# bms_board.net
KiCad netlist of a schematic drawn in EAGLE
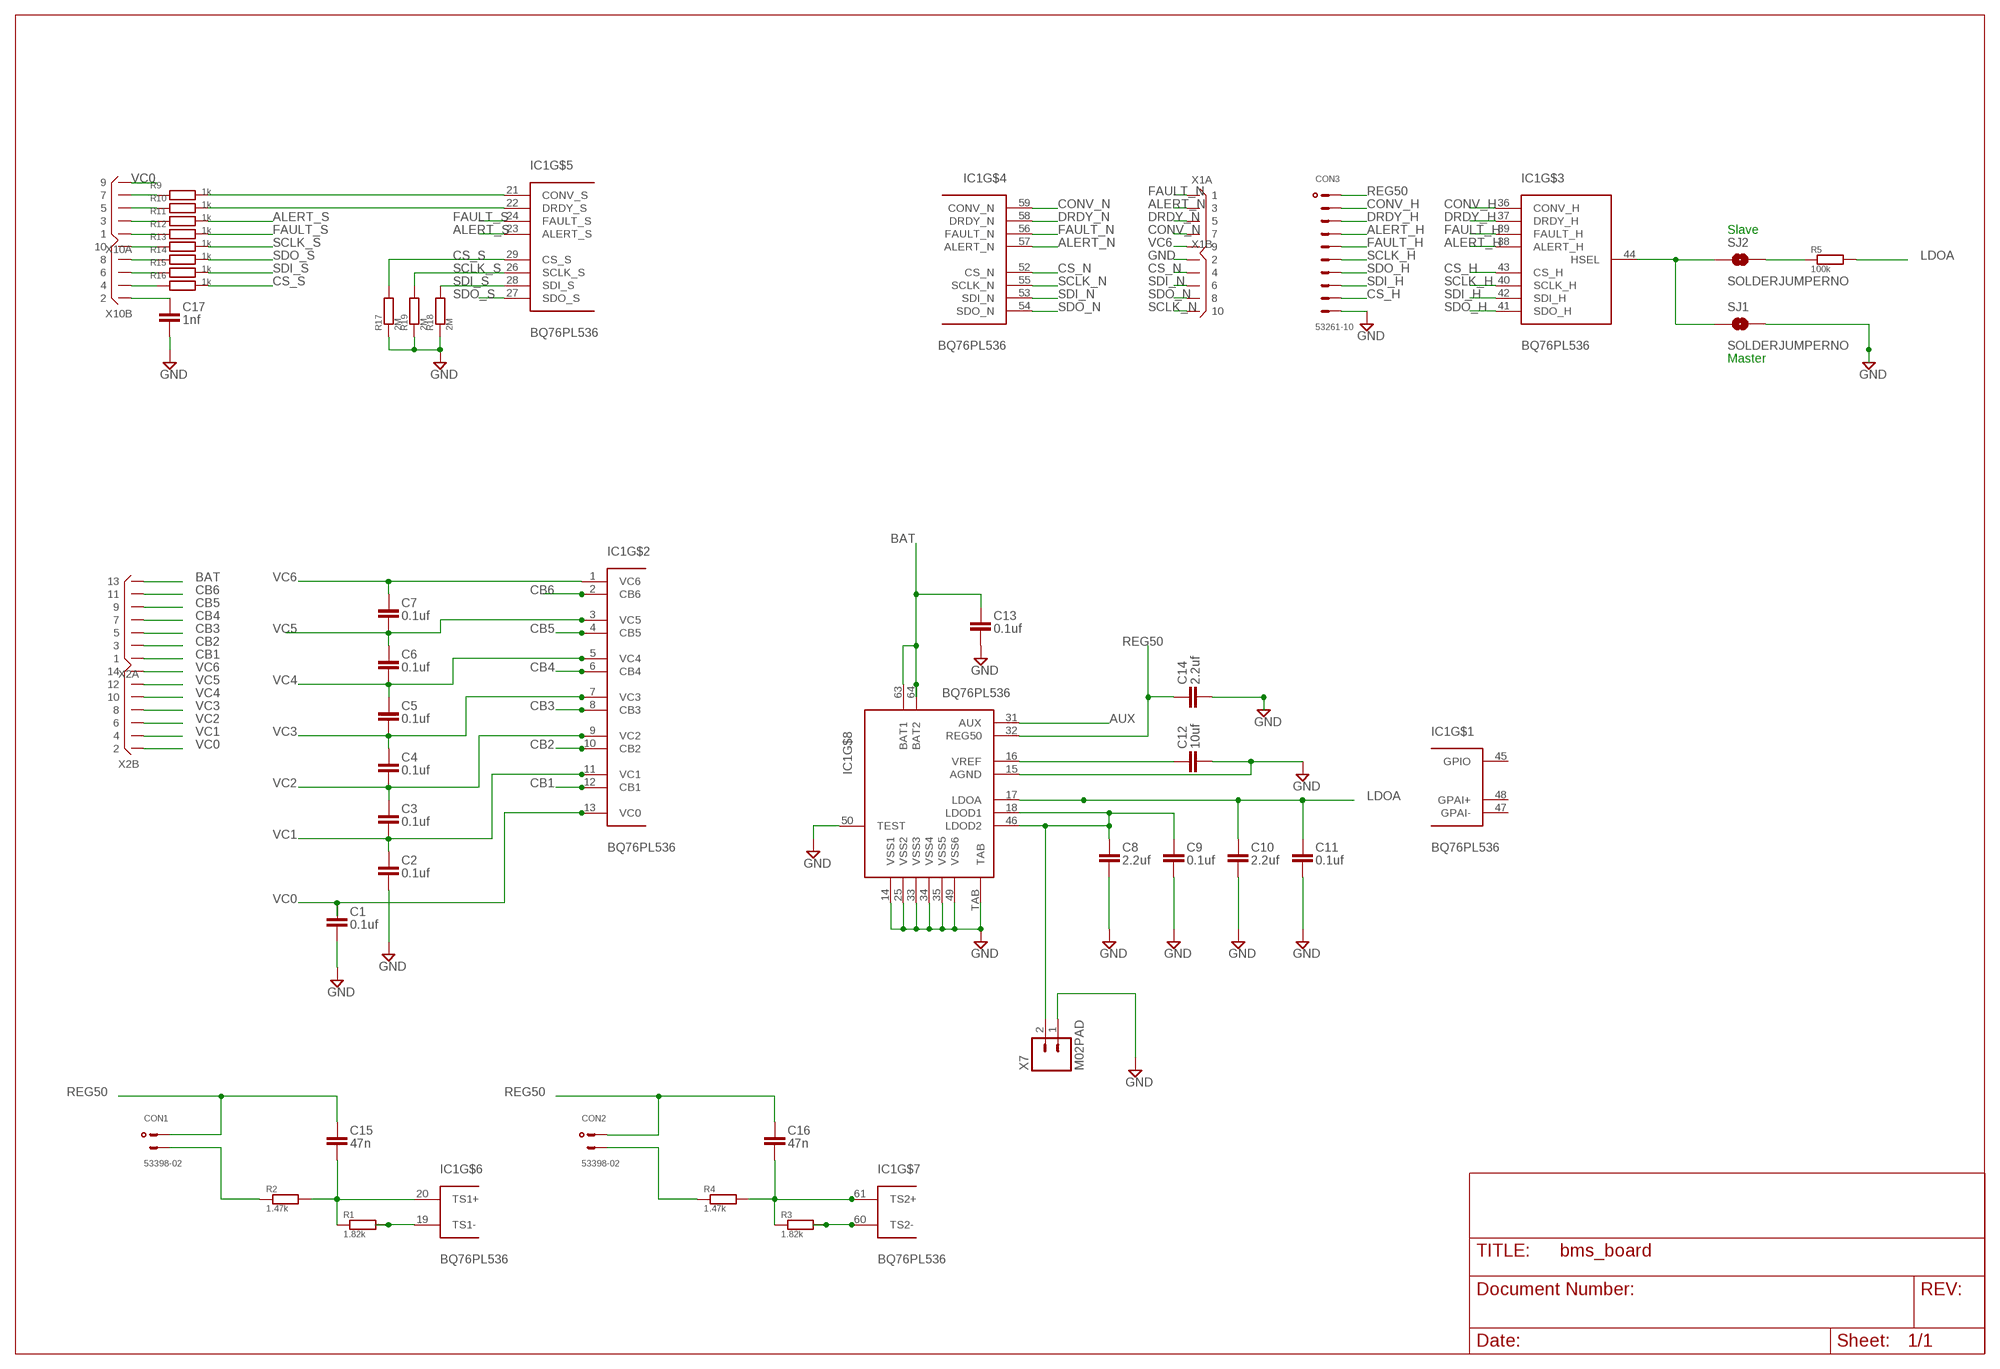
[diagram p0: schematic, sheet 1]

(export (version "E")
  (design (tool "Eeschema 10.0.6"))
  (components
    (comp (ref "C1")
      (value "0.1uf")
      (footprint "eagle-import:C0805")
      (libsource (lib "eagle-import") (part "CSTD"))
    )
    (comp (ref "C2")
      (value "0.1uf")
      (footprint "eagle-import:C0805")
      (libsource (lib "eagle-import") (part "CSTD"))
    )
    (comp (ref "C3")
      (value "0.1uf")
      (footprint "eagle-import:C0805")
      (libsource (lib "eagle-import") (part "CSTD"))
    )
    (comp (ref "C4")
      (value "0.1uf")
      (footprint "eagle-import:C0805")
      (libsource (lib "eagle-import") (part "CSTD"))
    )
    (comp (ref "C5")
      (value "0.1uf")
      (footprint "eagle-import:C0805")
      (libsource (lib "eagle-import") (part "CSTD"))
    )
    (comp (ref "C6")
      (value "0.1uf")
      (footprint "eagle-import:C0805")
      (libsource (lib "eagle-import") (part "CSTD"))
    )
    (comp (ref "C7")
      (value "0.1uf")
      (footprint "eagle-import:C0805")
      (libsource (lib "eagle-import") (part "CSTD"))
    )
    (comp (ref "C8")
      (value "2.2uf")
      (footprint "eagle-import:C0805")
      (libsource (lib "eagle-import") (part "CSTD"))
    )
    (comp (ref "C9")
      (value "0.1uf")
      (footprint "eagle-import:C0805")
      (libsource (lib "eagle-import") (part "CSTD"))
    )
    (comp (ref "C10")
      (value "2.2uf")
      (footprint "eagle-import:C0805")
      (libsource (lib "eagle-import") (part "CSTD"))
    )
    (comp (ref "C11")
      (value "0.1uf")
      (footprint "eagle-import:C0805")
      (libsource (lib "eagle-import") (part "CSTD"))
    )
    (comp (ref "C12")
      (value "10uf")
      (footprint "eagle-import:C0805")
      (libsource (lib "eagle-import") (part "CSTD"))
    )
    (comp (ref "C13")
      (value "0.1uf")
      (footprint "eagle-import:C0805")
      (libsource (lib "eagle-import") (part "CSTD"))
    )
    (comp (ref "C14")
      (value "2.2uf")
      (footprint "eagle-import:C0805")
      (libsource (lib "eagle-import") (part "CSTD"))
    )
    (comp (ref "C15")
      (value "47n")
      (footprint "eagle-import:C0805")
      (libsource (lib "eagle-import") (part "CSTD"))
    )
    (comp (ref "C16")
      (value "47n")
      (footprint "eagle-import:C0805")
      (libsource (lib "eagle-import") (part "CSTD"))
    )
    (comp (ref "C17")
      (value "1nf")
      (footprint "eagle-import:C0805")
      (libsource (lib "eagle-import") (part "CSTD"))
    )
    (comp (ref "CON1")
      (value "53398-02")
      (footprint "eagle-import:53398-02")
      (libsource (lib "eagle-import") (part "53?-02398"))
    )
    (comp (ref "CON2")
      (value "53398-02")
      (footprint "eagle-import:53398-02")
      (libsource (lib "eagle-import") (part "53?-02398"))
    )
    (comp (ref "CON3")
      (value "53261-10")
      (footprint "eagle-import:53261-10")
      (libsource (lib "eagle-import") (part "53?-10261"))
    )
    (comp (ref "IC1")
      (value "BQ76PL536")
      (footprint "eagle-import:LQFP-64")
      (libsource (lib "eagle-import") (part "BQ76PL536"))
    )
    (comp (ref "R1")
      (value "1.82k")
      (footprint "eagle-import:R0805")
      (libsource (lib "eagle-import") (part "R"))
    )
    (comp (ref "R2")
      (value "1.47k")
      (footprint "eagle-import:R0805")
      (libsource (lib "eagle-import") (part "R"))
    )
    (comp (ref "R3")
      (value "1.82k")
      (footprint "eagle-import:R0805")
      (libsource (lib "eagle-import") (part "R"))
    )
    (comp (ref "R4")
      (value "1.47k")
      (footprint "eagle-import:R0805")
      (libsource (lib "eagle-import") (part "R"))
    )
    (comp (ref "R5")
      (value "100k")
      (footprint "eagle-import:R0805")
      (libsource (lib "eagle-import") (part "R"))
    )
    (comp (ref "R9")
      (value "1k")
      (footprint "eagle-import:R0805")
      (libsource (lib "eagle-import") (part "R"))
    )
    (comp (ref "R10")
      (value "1k")
      (footprint "eagle-import:R0805")
      (libsource (lib "eagle-import") (part "R"))
    )
    (comp (ref "R11")
      (value "1k")
      (footprint "eagle-import:R0805")
      (libsource (lib "eagle-import") (part "R"))
    )
    (comp (ref "R12")
      (value "1k")
      (footprint "eagle-import:R0805")
      (libsource (lib "eagle-import") (part "R"))
    )
    (comp (ref "R13")
      (value "1k")
      (footprint "eagle-import:R0805")
      (libsource (lib "eagle-import") (part "R"))
    )
    (comp (ref "R14")
      (value "1k")
      (footprint "eagle-import:R0805")
      (libsource (lib "eagle-import") (part "R"))
    )
    (comp (ref "R15")
      (value "1k")
      (footprint "eagle-import:R0805")
      (libsource (lib "eagle-import") (part "R"))
    )
    (comp (ref "R16")
      (value "1k")
      (footprint "eagle-import:R0805")
      (libsource (lib "eagle-import") (part "R"))
    )
    (comp (ref "R17")
      (value "2M")
      (footprint "eagle-import:R0805")
      (libsource (lib "eagle-import") (part "R"))
    )
    (comp (ref "R18")
      (value "2M")
      (footprint "eagle-import:R0805")
      (libsource (lib "eagle-import") (part "R"))
    )
    (comp (ref "R19")
      (value "2M")
      (footprint "eagle-import:R0805")
      (libsource (lib "eagle-import") (part "R"))
    )
    (comp (ref "SJ1")
      (value "SOLDERJUMPERNO")
      (footprint "eagle-import:SJ_2S-NO")
      (libsource (lib "eagle-import") (part "SOLDERJUMPERNO"))
    )
    (comp (ref "SJ2")
      (value "SOLDERJUMPERNO")
      (footprint "eagle-import:SJ_2S-NO")
      (libsource (lib "eagle-import") (part "SOLDERJUMPERNO"))
    )
    (comp (ref "X1")
      (value "X05X2ICR")
      (footprint "eagle-import:X10ICR")
      (libsource (lib "eagle-import") (part "X05X2ICR"))
    )
    (comp (ref "X2")
      (value "X07X2IR")
      (footprint "eagle-import:X14R-IDC")
      (libsource (lib "eagle-import") (part "X07X2IR"))
    )
    (comp (ref "X7")
      (value "M02PAD")
      (footprint "eagle-import:1X02")
      (libsource (lib "eagle-import") (part "M02PAD"))
    )
    (comp (ref "X10")
      (value "X05X2ICR")
      (footprint "eagle-import:X10ICR")
      (libsource (lib "eagle-import") (part "X05X2ICR"))
    )
  )
  (nets
    (net (code "1") (name "/ALERT_H") (class "Default")
      (node (ref "CON3") (pin "4") (pinfunction "4_4") (pintype "passive"))
      (node (ref "IC1") (pin "38") (pinfunction "ALERT_H_38") (pintype "bidirectional"))
    )
    (net (code "2") (name "/ALERT_N") (class "Default")
      (node (ref "IC1") (pin "57") (pinfunction "ALERT_N_57") (pintype "bidirectional"))
      (node (ref "X1") (pin "3") (pinfunction "3_3") (pintype "bidirectional"))
    )
    (net (code "3") (name "/ALERT_S") (class "Default")
      (node (ref "IC1") (pin "23") (pinfunction "ALERT_S_23") (pintype "bidirectional"))
      (node (ref "R11") (pin "2") (pinfunction "2_2") (pintype "passive"))
    )
    (net (code "4") (name "/AUX") (class "Default")
      (node (ref "IC1") (pin "31") (pinfunction "AUX_31") (pintype "bidirectional"))
    )
    (net (code "5") (name "/BAT") (class "Default")
      (node (ref "C13") (pin "2") (pinfunction "2_2") (pintype "passive"))
      (node (ref "IC1") (pin "63") (pinfunction "BAT1_63") (pintype "bidirectional"))
      (node (ref "IC1") (pin "64") (pinfunction "BAT2_64") (pintype "bidirectional"))
      (node (ref "X2") (pin "13") (pinfunction "13_13") (pintype "bidirectional"))
    )
    (net (code "6") (name "/CB1") (class "Default")
      (node (ref "IC1") (pin "12") (pinfunction "CB1_12") (pintype "bidirectional"))
      (node (ref "X2") (pin "1") (pinfunction "1_1") (pintype "bidirectional"))
    )
    (net (code "7") (name "/CB2") (class "Default")
      (node (ref "IC1") (pin "10") (pinfunction "CB2_10") (pintype "bidirectional"))
      (node (ref "X2") (pin "3") (pinfunction "3_3") (pintype "bidirectional"))
    )
    (net (code "8") (name "/CB3") (class "Default")
      (node (ref "IC1") (pin "8") (pinfunction "CB3_8") (pintype "bidirectional"))
      (node (ref "X2") (pin "5") (pinfunction "5_5") (pintype "bidirectional"))
    )
    (net (code "9") (name "/CB4") (class "Default")
      (node (ref "IC1") (pin "6") (pinfunction "CB4_6") (pintype "bidirectional"))
      (node (ref "X2") (pin "7") (pinfunction "7_7") (pintype "bidirectional"))
    )
    (net (code "10") (name "/CB5") (class "Default")
      (node (ref "IC1") (pin "4") (pinfunction "CB5_4") (pintype "bidirectional"))
      (node (ref "X2") (pin "9") (pinfunction "9_9") (pintype "bidirectional"))
    )
    (net (code "11") (name "/CB6") (class "Default")
      (node (ref "IC1") (pin "2") (pinfunction "CB6_2") (pintype "bidirectional"))
      (node (ref "X2") (pin "11") (pinfunction "11_11") (pintype "bidirectional"))
    )
    (net (code "12") (name "/CONV_H") (class "Default")
      (node (ref "CON3") (pin "2") (pinfunction "2_2") (pintype "passive"))
      (node (ref "IC1") (pin "36") (pinfunction "CONV_H_36") (pintype "bidirectional"))
    )
    (net (code "13") (name "/CONV_N") (class "Default")
      (node (ref "IC1") (pin "59") (pinfunction "CONV_N_59") (pintype "bidirectional"))
      (node (ref "X1") (pin "7") (pinfunction "7_7") (pintype "bidirectional"))
    )
    (net (code "14") (name "/CS_H") (class "Default")
      (node (ref "CON3") (pin "9") (pinfunction "9_9") (pintype "passive"))
      (node (ref "IC1") (pin "43") (pinfunction "CS_H_43") (pintype "bidirectional"))
    )
    (net (code "15") (name "/CS_N") (class "Default")
      (node (ref "IC1") (pin "52") (pinfunction "CS_N_52") (pintype "bidirectional"))
      (node (ref "X1") (pin "4") (pinfunction "4_4") (pintype "bidirectional"))
    )
    (net (code "16") (name "/CS_S") (class "Default")
      (node (ref "IC1") (pin "29") (pinfunction "CS_S_29") (pintype "bidirectional"))
      (node (ref "R16") (pin "2") (pinfunction "2_2") (pintype "passive"))
      (node (ref "R17") (pin "2") (pinfunction "2_2") (pintype "passive"))
    )
    (net (code "17") (name "/DRDY_H") (class "Default")
      (node (ref "CON3") (pin "3") (pinfunction "3_3") (pintype "passive"))
      (node (ref "IC1") (pin "37") (pinfunction "DRDY_H_37") (pintype "bidirectional"))
    )
    (net (code "18") (name "/DRDY_N") (class "Default")
      (node (ref "IC1") (pin "58") (pinfunction "DRDY_N_58") (pintype "bidirectional"))
      (node (ref "X1") (pin "5") (pinfunction "5_5") (pintype "bidirectional"))
    )
    (net (code "19") (name "/FAULT_H") (class "Default")
      (node (ref "CON3") (pin "5") (pinfunction "5_5") (pintype "passive"))
      (node (ref "IC1") (pin "39") (pinfunction "FAULT_H_39") (pintype "bidirectional"))
    )
    (net (code "20") (name "/FAULT_N") (class "Default")
      (node (ref "IC1") (pin "56") (pinfunction "FAULT_N_56") (pintype "bidirectional"))
      (node (ref "X1") (pin "1") (pinfunction "1_1") (pintype "bidirectional"))
    )
    (net (code "21") (name "/FAULT_S") (class "Default")
      (node (ref "IC1") (pin "24") (pinfunction "FAULT_S_24") (pintype "bidirectional"))
      (node (ref "R12") (pin "2") (pinfunction "2_2") (pintype "passive"))
    )
    (net (code "22") (name "/LDOA") (class "Default")
      (node (ref "C10") (pin "2") (pinfunction "2_2") (pintype "passive"))
      (node (ref "C11") (pin "2") (pinfunction "2_2") (pintype "passive"))
      (node (ref "IC1") (pin "17") (pinfunction "LDOA_17") (pintype "bidirectional"))
      (node (ref "R5") (pin "2") (pinfunction "2_2") (pintype "passive"))
    )
    (net (code "23") (name "/REG50") (class "Default")
      (node (ref "C14") (pin "2") (pinfunction "2_2") (pintype "passive"))
      (node (ref "C15") (pin "2") (pinfunction "2_2") (pintype "passive"))
      (node (ref "C16") (pin "2") (pinfunction "2_2") (pintype "passive"))
      (node (ref "CON1") (pin "1") (pinfunction "1_1") (pintype "passive"))
      (node (ref "CON2") (pin "1") (pinfunction "1_1") (pintype "passive"))
      (node (ref "CON3") (pin "1") (pinfunction "1_1") (pintype "passive"))
      (node (ref "IC1") (pin "32") (pinfunction "REG50_32") (pintype "bidirectional"))
    )
    (net (code "24") (name "/SCLK_H") (class "Default")
      (node (ref "CON3") (pin "6") (pinfunction "6_6") (pintype "passive"))
      (node (ref "IC1") (pin "40") (pinfunction "SCLK_H_40") (pintype "bidirectional"))
    )
    (net (code "25") (name "/SCLK_N") (class "Default")
      (node (ref "IC1") (pin "55") (pinfunction "SCLK_N_55") (pintype "bidirectional"))
      (node (ref "X1") (pin "10") (pinfunction "10_10") (pintype "bidirectional"))
    )
    (net (code "26") (name "/SCLK_S") (class "Default")
      (node (ref "IC1") (pin "26") (pinfunction "SCLK_S_26") (pintype "bidirectional"))
      (node (ref "R13") (pin "2") (pinfunction "2_2") (pintype "passive"))
      (node (ref "R19") (pin "2") (pinfunction "2_2") (pintype "passive"))
    )
    (net (code "27") (name "/SDI_H") (class "Default")
      (node (ref "CON3") (pin "8") (pinfunction "8_8") (pintype "passive"))
      (node (ref "IC1") (pin "42") (pinfunction "SDI_H_42") (pintype "bidirectional"))
    )
    (net (code "28") (name "/SDI_N") (class "Default")
      (node (ref "IC1") (pin "53") (pinfunction "SDI_N_53") (pintype "bidirectional"))
      (node (ref "X1") (pin "6") (pinfunction "6_6") (pintype "bidirectional"))
    )
    (net (code "29") (name "/SDI_S") (class "Default")
      (node (ref "IC1") (pin "28") (pinfunction "SDI_S_28") (pintype "bidirectional"))
      (node (ref "R15") (pin "2") (pinfunction "2_2") (pintype "passive"))
      (node (ref "R18") (pin "2") (pinfunction "2_2") (pintype "passive"))
    )
    (net (code "30") (name "/SDO_H") (class "Default")
      (node (ref "CON3") (pin "7") (pinfunction "7_7") (pintype "passive"))
      (node (ref "IC1") (pin "41") (pinfunction "SDO_H_41") (pintype "bidirectional"))
    )
    (net (code "31") (name "/SDO_N") (class "Default")
      (node (ref "IC1") (pin "54") (pinfunction "SDO_N_54") (pintype "bidirectional"))
      (node (ref "X1") (pin "8") (pinfunction "8_8") (pintype "bidirectional"))
    )
    (net (code "32") (name "/SDO_S") (class "Default")
      (node (ref "IC1") (pin "27") (pinfunction "SDO_S_27") (pintype "bidirectional"))
      (node (ref "R14") (pin "2") (pinfunction "2_2") (pintype "passive"))
    )
    (net (code "33") (name "/VC0") (class "Default")
      (node (ref "C1") (pin "2") (pinfunction "2_2") (pintype "passive"))
      (node (ref "IC1") (pin "13") (pinfunction "VC0_13") (pintype "bidirectional"))
      (node (ref "X10") (pin "9") (pinfunction "9_9") (pintype "bidirectional"))
      (node (ref "X2") (pin "2") (pinfunction "2_2") (pintype "bidirectional"))
    )
    (net (code "34") (name "/VC1") (class "Default")
      (node (ref "C2") (pin "2") (pinfunction "2_2") (pintype "passive"))
      (node (ref "C3") (pin "1") (pinfunction "1_1") (pintype "passive"))
      (node (ref "IC1") (pin "11") (pinfunction "VC1_11") (pintype "bidirectional"))
      (node (ref "X2") (pin "4") (pinfunction "4_4") (pintype "bidirectional"))
    )
    (net (code "35") (name "/VC2") (class "Default")
      (node (ref "C3") (pin "2") (pinfunction "2_2") (pintype "passive"))
      (node (ref "C4") (pin "1") (pinfunction "1_1") (pintype "passive"))
      (node (ref "IC1") (pin "9") (pinfunction "VC2_9") (pintype "bidirectional"))
      (node (ref "X2") (pin "6") (pinfunction "6_6") (pintype "bidirectional"))
    )
    (net (code "36") (name "/VC3") (class "Default")
      (node (ref "C4") (pin "2") (pinfunction "2_2") (pintype "passive"))
      (node (ref "C5") (pin "1") (pinfunction "1_1") (pintype "passive"))
      (node (ref "IC1") (pin "7") (pinfunction "VC3_7") (pintype "bidirectional"))
      (node (ref "X2") (pin "8") (pinfunction "8_8") (pintype "bidirectional"))
    )
    (net (code "37") (name "/VC4") (class "Default")
      (node (ref "C5") (pin "2") (pinfunction "2_2") (pintype "passive"))
      (node (ref "C6") (pin "1") (pinfunction "1_1") (pintype "passive"))
      (node (ref "IC1") (pin "5") (pinfunction "VC4_5") (pintype "bidirectional"))
      (node (ref "X2") (pin "10") (pinfunction "10_10") (pintype "bidirectional"))
    )
    (net (code "38") (name "/VC5") (class "Default")
      (node (ref "C6") (pin "2") (pinfunction "2_2") (pintype "passive"))
      (node (ref "C7") (pin "1") (pinfunction "1_1") (pintype "passive"))
      (node (ref "IC1") (pin "3") (pinfunction "VC5_3") (pintype "bidirectional"))
      (node (ref "X2") (pin "12") (pinfunction "12_12") (pintype "bidirectional"))
    )
    (net (code "39") (name "/VC6") (class "Default")
      (node (ref "C7") (pin "2") (pinfunction "2_2") (pintype "passive"))
      (node (ref "IC1") (pin "1") (pinfunction "VC6_1") (pintype "bidirectional"))
      (node (ref "X1") (pin "9") (pinfunction "9_9") (pintype "bidirectional"))
      (node (ref "X2") (pin "14") (pinfunction "14_14") (pintype "bidirectional"))
    )
    (net (code "40") (name "GND") (class "Default")
      (node (ref "C1") (pin "1") (pinfunction "1_1") (pintype "passive"))
      (node (ref "C10") (pin "1") (pinfunction "1_1") (pintype "passive"))
      (node (ref "C11") (pin "1") (pinfunction "1_1") (pintype "passive"))
      (node (ref "C12") (pin "1") (pinfunction "1_1") (pintype "passive"))
      (node (ref "C13") (pin "1") (pinfunction "1_1") (pintype "passive"))
      (node (ref "C14") (pin "1") (pinfunction "1_1") (pintype "passive"))
      (node (ref "C17") (pin "1") (pinfunction "1_1") (pintype "passive"))
      (node (ref "C2") (pin "1") (pinfunction "1_1") (pintype "passive"))
      (node (ref "C8") (pin "1") (pinfunction "1_1") (pintype "passive"))
      (node (ref "C9") (pin "1") (pinfunction "1_1") (pintype "passive"))
      (node (ref "CON3") (pin "10") (pinfunction "10_10") (pintype "passive"))
      (node (ref "IC1") (pin "14") (pinfunction "VSS1_14") (pintype "bidirectional"))
      (node (ref "IC1") (pin "15") (pinfunction "AGND_15") (pintype "bidirectional"))
      (node (ref "IC1") (pin "25") (pinfunction "VSS2_25") (pintype "bidirectional"))
      (node (ref "IC1") (pin "33") (pinfunction "VSS3_33") (pintype "bidirectional"))
      (node (ref "IC1") (pin "34") (pinfunction "VSS4_34") (pintype "bidirectional"))
      (node (ref "IC1") (pin "35") (pinfunction "VSS5_35") (pintype "bidirectional"))
      (node (ref "IC1") (pin "49") (pinfunction "VSS6_49") (pintype "bidirectional"))
      (node (ref "IC1") (pin "50") (pinfunction "TEST_50") (pintype "bidirectional"))
      (node (ref "IC1") (pin "TAB") (pinfunction "TAB_TAB") (pintype "bidirectional"))
      (node (ref "R17") (pin "1") (pinfunction "1_1") (pintype "passive"))
      (node (ref "R18") (pin "1") (pinfunction "1_1") (pintype "passive"))
      (node (ref "R19") (pin "1") (pinfunction "1_1") (pintype "passive"))
      (node (ref "SJ1") (pin "2") (pinfunction "2_2") (pintype "passive"))
      (node (ref "X1") (pin "2") (pinfunction "2_2") (pintype "bidirectional"))
      (node (ref "X7") (pin "1") (pinfunction "1_1") (pintype "passive"))
    )
    (net (code "41") (name "Net-(C17-Pad2)") (class "Default")
      (node (ref "C17") (pin "2") (pinfunction "2_2") (pintype "passive"))
      (node (ref "X10") (pin "2") (pinfunction "2_2") (pintype "bidirectional"))
    )
    (net (code "42") (name "Net-(CON1-Pad2)") (class "Default")
      (node (ref "CON1") (pin "2") (pinfunction "2_2") (pintype "passive"))
      (node (ref "R2") (pin "1") (pinfunction "1_1") (pintype "passive"))
    )
    (net (code "43") (name "Net-(CON2-Pad2)") (class "Default")
      (node (ref "CON2") (pin "2") (pinfunction "2_2") (pintype "passive"))
      (node (ref "R4") (pin "1") (pinfunction "1_1") (pintype "passive"))
    )
    (net (code "44") (name "Net-(IC1C-HSEL)") (class "Default")
      (node (ref "IC1") (pin "44") (pinfunction "HSEL_44") (pintype "bidirectional"))
      (node (ref "SJ1") (pin "1") (pinfunction "1_1") (pintype "passive"))
      (node (ref "SJ2") (pin "1") (pinfunction "1_1") (pintype "passive"))
    )
    (net (code "45") (name "Net-(IC1E-CONV_S)") (class "Default")
      (node (ref "IC1") (pin "21") (pinfunction "CONV_S_21") (pintype "bidirectional"))
      (node (ref "R9") (pin "2") (pinfunction "2_2") (pintype "passive"))
    )
    (net (code "46") (name "Net-(IC1E-DRDY_S)") (class "Default")
      (node (ref "IC1") (pin "22") (pinfunction "DRDY_S_22") (pintype "bidirectional"))
      (node (ref "R10") (pin "2") (pinfunction "2_2") (pintype "passive"))
    )
    (net (code "47") (name "Net-(IC1F-TS1+)") (class "Default")
      (node (ref "C15") (pin "1") (pinfunction "1_1") (pintype "passive"))
      (node (ref "IC1") (pin "20") (pinfunction "TS1+_20") (pintype "bidirectional"))
      (node (ref "R1") (pin "1") (pinfunction "1_1") (pintype "passive"))
      (node (ref "R2") (pin "2") (pinfunction "2_2") (pintype "passive"))
    )
    (net (code "48") (name "Net-(IC1F-TS1-)") (class "Default")
      (node (ref "IC1") (pin "19") (pinfunction "TS1-_19") (pintype "bidirectional"))
      (node (ref "R1") (pin "2") (pinfunction "2_2") (pintype "passive"))
    )
    (net (code "49") (name "Net-(IC1G-TS2+)") (class "Default")
      (node (ref "C16") (pin "1") (pinfunction "1_1") (pintype "passive"))
      (node (ref "IC1") (pin "61") (pinfunction "TS2+_61") (pintype "bidirectional"))
      (node (ref "R3") (pin "1") (pinfunction "1_1") (pintype "passive"))
      (node (ref "R4") (pin "2") (pinfunction "2_2") (pintype "passive"))
    )
    (net (code "50") (name "Net-(IC1G-TS2-)") (class "Default")
      (node (ref "IC1") (pin "60") (pinfunction "TS2-_60") (pintype "bidirectional"))
      (node (ref "R3") (pin "2") (pinfunction "2_2") (pintype "passive"))
    )
    (net (code "51") (name "Net-(IC1H-LDOD1)") (class "Default")
      (node (ref "C8") (pin "2") (pinfunction "2_2") (pintype "passive"))
      (node (ref "C9") (pin "2") (pinfunction "2_2") (pintype "passive"))
      (node (ref "IC1") (pin "18") (pinfunction "LDOD1_18") (pintype "bidirectional"))
      (node (ref "IC1") (pin "46") (pinfunction "LDOD2_46") (pintype "bidirectional"))
      (node (ref "X7") (pin "2") (pinfunction "2_2") (pintype "passive"))
    )
    (net (code "52") (name "Net-(IC1H-VREF)") (class "Default")
      (node (ref "C12") (pin "2") (pinfunction "2_2") (pintype "passive"))
      (node (ref "IC1") (pin "16") (pinfunction "VREF_16") (pintype "bidirectional"))
    )
    (net (code "53") (name "Net-(R5-Pad1)") (class "Default")
      (node (ref "R5") (pin "1") (pinfunction "1_1") (pintype "passive"))
      (node (ref "SJ2") (pin "2") (pinfunction "2_2") (pintype "passive"))
    )
    (net (code "54") (name "Net-(R9-Pad1)") (class "Default")
      (node (ref "R9") (pin "1") (pinfunction "1_1") (pintype "passive"))
      (node (ref "X10") (pin "7") (pinfunction "7_7") (pintype "bidirectional"))
    )
    (net (code "55") (name "Net-(R10-Pad1)") (class "Default")
      (node (ref "R10") (pin "1") (pinfunction "1_1") (pintype "passive"))
      (node (ref "X10") (pin "5") (pinfunction "5_5") (pintype "bidirectional"))
    )
    (net (code "56") (name "Net-(R11-Pad1)") (class "Default")
      (node (ref "R11") (pin "1") (pinfunction "1_1") (pintype "passive"))
      (node (ref "X10") (pin "3") (pinfunction "3_3") (pintype "bidirectional"))
    )
    (net (code "57") (name "Net-(R12-Pad1)") (class "Default")
      (node (ref "R12") (pin "1") (pinfunction "1_1") (pintype "passive"))
      (node (ref "X10") (pin "1") (pinfunction "1_1") (pintype "bidirectional"))
    )
    (net (code "58") (name "Net-(R13-Pad1)") (class "Default")
      (node (ref "R13") (pin "1") (pinfunction "1_1") (pintype "passive"))
      (node (ref "X10") (pin "10") (pinfunction "10_10") (pintype "bidirectional"))
    )
    (net (code "59") (name "Net-(R14-Pad1)") (class "Default")
      (node (ref "R14") (pin "1") (pinfunction "1_1") (pintype "passive"))
      (node (ref "X10") (pin "8") (pinfunction "8_8") (pintype "bidirectional"))
    )
    (net (code "60") (name "Net-(R15-Pad1)") (class "Default")
      (node (ref "R15") (pin "1") (pinfunction "1_1") (pintype "passive"))
      (node (ref "X10") (pin "6") (pinfunction "6_6") (pintype "bidirectional"))
    )
    (net (code "61") (name "Net-(R16-Pad1)") (class "Default")
      (node (ref "R16") (pin "1") (pinfunction "1_1") (pintype "passive"))
      (node (ref "X10") (pin "4") (pinfunction "4_4") (pintype "bidirectional"))
    )
    (net (code "62") (name "unconnected-(IC1A-GPAI+-Pad48)") (class "Default")
      (node (ref "IC1") (pin "48") (pinfunction "GPAI+_48") (pintype "bidirectional"))
    )
    (net (code "63") (name "unconnected-(IC1A-GPAI--Pad47)") (class "Default")
      (node (ref "IC1") (pin "47") (pinfunction "GPAI-_47") (pintype "bidirectional"))
    )
    (net (code "64") (name "unconnected-(IC1A-GPIO-Pad45)") (class "Default")
      (node (ref "IC1") (pin "45") (pinfunction "GPIO_45") (pintype "bidirectional"))
    )
  )
)
